# 130_Pad.net
KiCad netlist of a schematic drawn in EAGLE
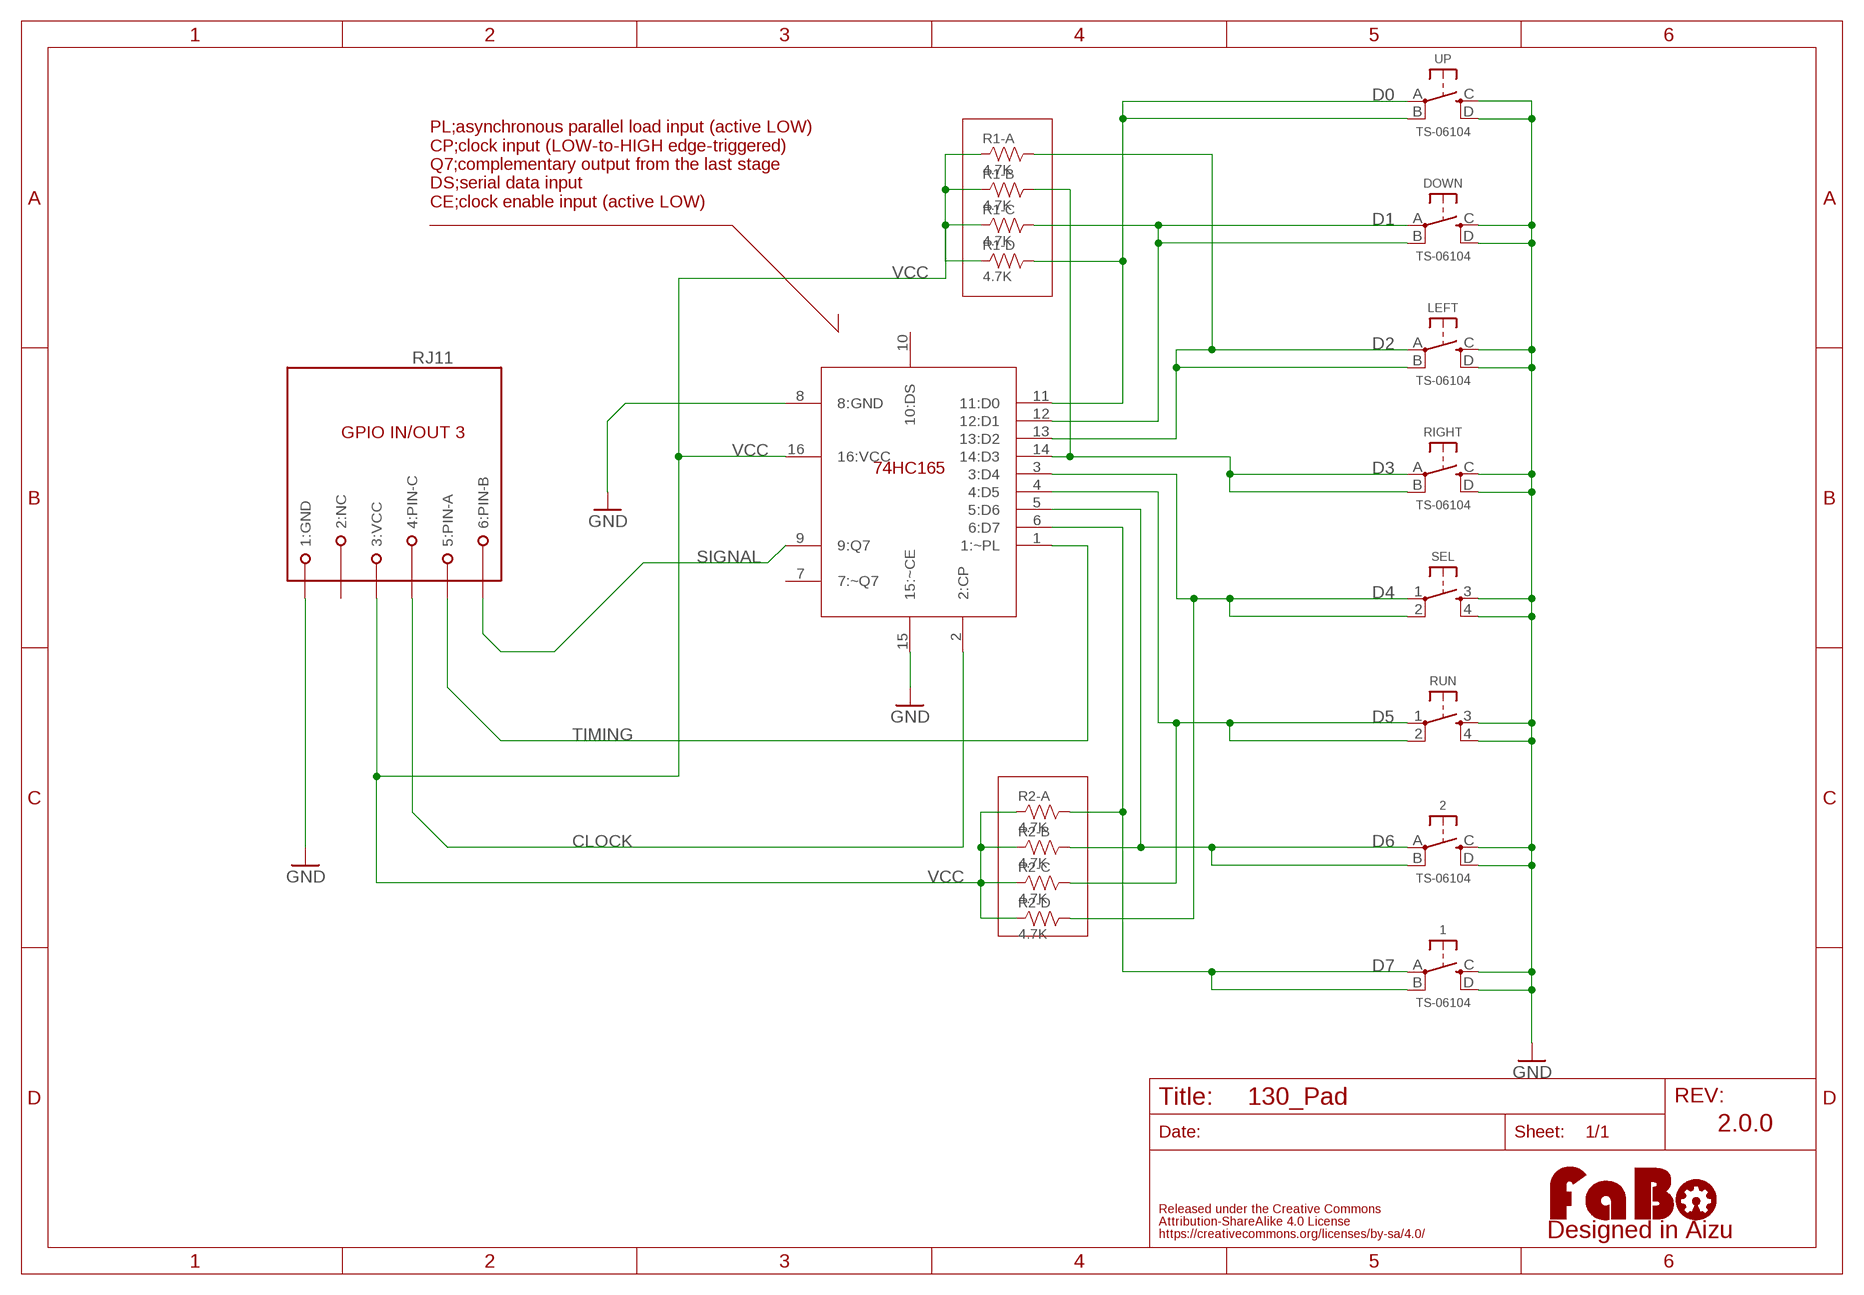
[diagram p0: schematic, sheet 1]

(export (version "E")
  (design (tool "Eeschema 10.0.6"))
  (components
    (comp (ref "1")
      (value "TS-06104")
      (footprint "eagle-import:TS-06104")
      (libsource (lib "eagle-import") (part "TS-06104"))
    )
    (comp (ref "2")
      (value "TS-06104")
      (footprint "eagle-import:TS-06104")
      (libsource (lib "eagle-import") (part "TS-06104"))
    )
    (comp (ref "DOWN")
      (value "TS-06104")
      (footprint "eagle-import:TS-06104")
      (libsource (lib "eagle-import") (part "TS-06104"))
    )
    (comp (ref "LEFT")
      (value "TS-06104")
      (footprint "eagle-import:TS-06104")
      (libsource (lib "eagle-import") (part "TS-06104"))
    )
    (comp (ref "LOGO1")
      (value "LOGO_FABO-M_BOTTOM")
      (footprint "eagle-import:LOGO_FABO_M_BOTTOM")
      (libsource (lib "eagle-import") (part "LOGO_FABO-M_BOTTOM"))
    )
    (comp (ref "R1")
      (value "4.7K")
      (footprint "eagle-import:EXBV8V")
      (libsource (lib "eagle-import") (part "RESISTOR_ARRAY_4"))
    )
    (comp (ref "R2")
      (value "4.7K")
      (footprint "eagle-import:EXBV8V")
      (libsource (lib "eagle-import") (part "RESISTOR_ARRAY_4"))
    )
    (comp (ref "RIGHT")
      (value "TS-06104")
      (footprint "eagle-import:TS-06104")
      (libsource (lib "eagle-import") (part "TS-06104"))
    )
    (comp (ref "RJ11")
      (value "MODULAR-JACK-6P-RJ11_GPIO3")
      (footprint "eagle-import:7002-6PXC-X")
      (libsource (lib "eagle-import") (part "MODULAR-JACK-6P-RJ11_GPIO3"))
    )
    (comp (ref "RUN")
      (value "TACT-SWITCH-SMD_KMR2")
      (footprint "eagle-import:KMR2")
      (libsource (lib "eagle-import") (part "TACT-SWITCH-SMD_KMR2"))
    )
    (comp (ref "SEL")
      (value "TACT-SWITCH-SMD_KMR2")
      (footprint "eagle-import:KMR2")
      (libsource (lib "eagle-import") (part "TACT-SWITCH-SMD_KMR2"))
    )
    (comp (ref "U$5")
      (value "74HC165")
      (footprint "eagle-import:SO16")
      (libsource (lib "eagle-import") (part "74HC165"))
    )
    (comp (ref "UP")
      (value "TS-06104")
      (footprint "eagle-import:TS-06104")
      (libsource (lib "eagle-import") (part "TS-06104"))
    )
  )
  (nets
    (net (code "1") (name "/CLOCK") (class "Default")
      (node (ref "RJ11") (pin "4") (pinfunction "4:PIN-C_4") (pintype "bidirectional"))
      (node (ref "U$5") (pin "2") (pinfunction "2:CP_2") (pintype "bidirectional"))
    )
    (net (code "2") (name "/D0") (class "Default")
      (node (ref "R1") (pin "5") (pinfunction "2_5") (pintype "bidirectional"))
      (node (ref "U$5") (pin "11") (pinfunction "11:D0_11") (pintype "bidirectional"))
      (node (ref "UP") (pin "A") (pinfunction "A_A") (pintype "passive"))
      (node (ref "UP") (pin "B") (pinfunction "B_B") (pintype "passive"))
    )
    (net (code "3") (name "/D1") (class "Default")
      (node (ref "DOWN") (pin "A") (pinfunction "A_A") (pintype "passive"))
      (node (ref "DOWN") (pin "B") (pinfunction "B_B") (pintype "passive"))
      (node (ref "R1") (pin "6") (pinfunction "2_6") (pintype "bidirectional"))
      (node (ref "U$5") (pin "12") (pinfunction "12:D1_12") (pintype "bidirectional"))
    )
    (net (code "4") (name "/D2") (class "Default")
      (node (ref "LEFT") (pin "A") (pinfunction "A_A") (pintype "passive"))
      (node (ref "LEFT") (pin "B") (pinfunction "B_B") (pintype "passive"))
      (node (ref "R1") (pin "8") (pinfunction "2_8") (pintype "bidirectional"))
      (node (ref "U$5") (pin "13") (pinfunction "13:D2_13") (pintype "bidirectional"))
    )
    (net (code "5") (name "/D3") (class "Default")
      (node (ref "R1") (pin "7") (pinfunction "2_7") (pintype "bidirectional"))
      (node (ref "RIGHT") (pin "A") (pinfunction "A_A") (pintype "passive"))
      (node (ref "RIGHT") (pin "B") (pinfunction "B_B") (pintype "passive"))
      (node (ref "U$5") (pin "14") (pinfunction "14:D3_14") (pintype "bidirectional"))
    )
    (net (code "6") (name "/D4") (class "Default")
      (node (ref "R2") (pin "5") (pinfunction "2_5") (pintype "bidirectional"))
      (node (ref "SEL") (pin "1") (pinfunction "1_1") (pintype "passive"))
      (node (ref "SEL") (pin "2") (pinfunction "2_2") (pintype "passive"))
      (node (ref "U$5") (pin "3") (pinfunction "3:D4_3") (pintype "bidirectional"))
    )
    (net (code "7") (name "/D5") (class "Default")
      (node (ref "R2") (pin "6") (pinfunction "2_6") (pintype "bidirectional"))
      (node (ref "RUN") (pin "1") (pinfunction "1_1") (pintype "passive"))
      (node (ref "RUN") (pin "2") (pinfunction "2_2") (pintype "passive"))
      (node (ref "U$5") (pin "4") (pinfunction "4:D5_4") (pintype "bidirectional"))
    )
    (net (code "8") (name "/D6") (class "Default")
      (node (ref "2") (pin "A") (pinfunction "A_A") (pintype "passive"))
      (node (ref "2") (pin "B") (pinfunction "B_B") (pintype "passive"))
      (node (ref "R2") (pin "7") (pinfunction "2_7") (pintype "bidirectional"))
      (node (ref "U$5") (pin "5") (pinfunction "5:D6_5") (pintype "bidirectional"))
    )
    (net (code "9") (name "/D7") (class "Default")
      (node (ref "1") (pin "A") (pinfunction "A_A") (pintype "passive"))
      (node (ref "1") (pin "B") (pinfunction "B_B") (pintype "passive"))
      (node (ref "R2") (pin "8") (pinfunction "2_8") (pintype "bidirectional"))
      (node (ref "U$5") (pin "6") (pinfunction "6:D7_6") (pintype "bidirectional"))
    )
    (net (code "10") (name "/SIGNAL") (class "Default")
      (node (ref "RJ11") (pin "6") (pinfunction "6:PIN-B_6") (pintype "bidirectional"))
      (node (ref "U$5") (pin "9") (pinfunction "9:Q7_9") (pintype "bidirectional"))
    )
    (net (code "11") (name "/TIMING") (class "Default")
      (node (ref "RJ11") (pin "5") (pinfunction "5:PIN-A_5") (pintype "bidirectional"))
      (node (ref "U$5") (pin "1") (pinfunction "1:~{PL}_1") (pintype "bidirectional"))
    )
    (net (code "12") (name "/VCC") (class "Default")
      (node (ref "R1") (pin "1") (pinfunction "1_1") (pintype "bidirectional"))
      (node (ref "R1") (pin "2") (pinfunction "1_2") (pintype "bidirectional"))
      (node (ref "R1") (pin "3") (pinfunction "1_3") (pintype "bidirectional"))
      (node (ref "R1") (pin "4") (pinfunction "1_4") (pintype "bidirectional"))
      (node (ref "R2") (pin "1") (pinfunction "1_1") (pintype "bidirectional"))
      (node (ref "R2") (pin "2") (pinfunction "1_2") (pintype "bidirectional"))
      (node (ref "R2") (pin "3") (pinfunction "1_3") (pintype "bidirectional"))
      (node (ref "R2") (pin "4") (pinfunction "1_4") (pintype "bidirectional"))
      (node (ref "RJ11") (pin "3") (pinfunction "3:VCC_3") (pintype "power_in"))
      (node (ref "U$5") (pin "16") (pinfunction "16:VCC_16") (pintype "bidirectional"))
    )
    (net (code "13") (name "GND") (class "Default")
      (node (ref "1") (pin "C") (pinfunction "C_C") (pintype "passive"))
      (node (ref "1") (pin "D") (pinfunction "D_D") (pintype "passive"))
      (node (ref "2") (pin "C") (pinfunction "C_C") (pintype "passive"))
      (node (ref "2") (pin "D") (pinfunction "D_D") (pintype "passive"))
      (node (ref "DOWN") (pin "C") (pinfunction "C_C") (pintype "passive"))
      (node (ref "DOWN") (pin "D") (pinfunction "D_D") (pintype "passive"))
      (node (ref "LEFT") (pin "C") (pinfunction "C_C") (pintype "passive"))
      (node (ref "LEFT") (pin "D") (pinfunction "D_D") (pintype "passive"))
      (node (ref "RIGHT") (pin "C") (pinfunction "C_C") (pintype "passive"))
      (node (ref "RIGHT") (pin "D") (pinfunction "D_D") (pintype "passive"))
      (node (ref "RJ11") (pin "1") (pinfunction "1:GND_1") (pintype "power_in"))
      (node (ref "RUN") (pin "3") (pinfunction "3_3") (pintype "passive"))
      (node (ref "RUN") (pin "4") (pinfunction "4_4") (pintype "passive"))
      (node (ref "SEL") (pin "3") (pinfunction "3_3") (pintype "passive"))
      (node (ref "SEL") (pin "4") (pinfunction "4_4") (pintype "passive"))
      (node (ref "U$5") (pin "15") (pinfunction "15:~{CE}_15") (pintype "bidirectional"))
      (node (ref "U$5") (pin "8") (pinfunction "8:GND_8") (pintype "bidirectional"))
      (node (ref "UP") (pin "C") (pinfunction "C_C") (pintype "passive"))
      (node (ref "UP") (pin "D") (pinfunction "D_D") (pintype "passive"))
    )
    (net (code "14") (name "unconnected-(RJ11-2:NC-Pad2)") (class "Default")
      (node (ref "RJ11") (pin "2") (pinfunction "2:NC_2") (pintype "no_connect"))
    )
    (net (code "15") (name "unconnected-(U$5-7:~{Q7}-Pad7)") (class "Default")
      (node (ref "U$5") (pin "7") (pinfunction "7:~{Q7}_7") (pintype "bidirectional"))
    )
    (net (code "16") (name "unconnected-(U$5-10:DS-Pad10)") (class "Default")
      (node (ref "U$5") (pin "10") (pinfunction "10:DS_10") (pintype "bidirectional"))
    )
  )
)
